# US_SB_BIC.net
KiCad netlist of a schematic drawn in Altium Designer
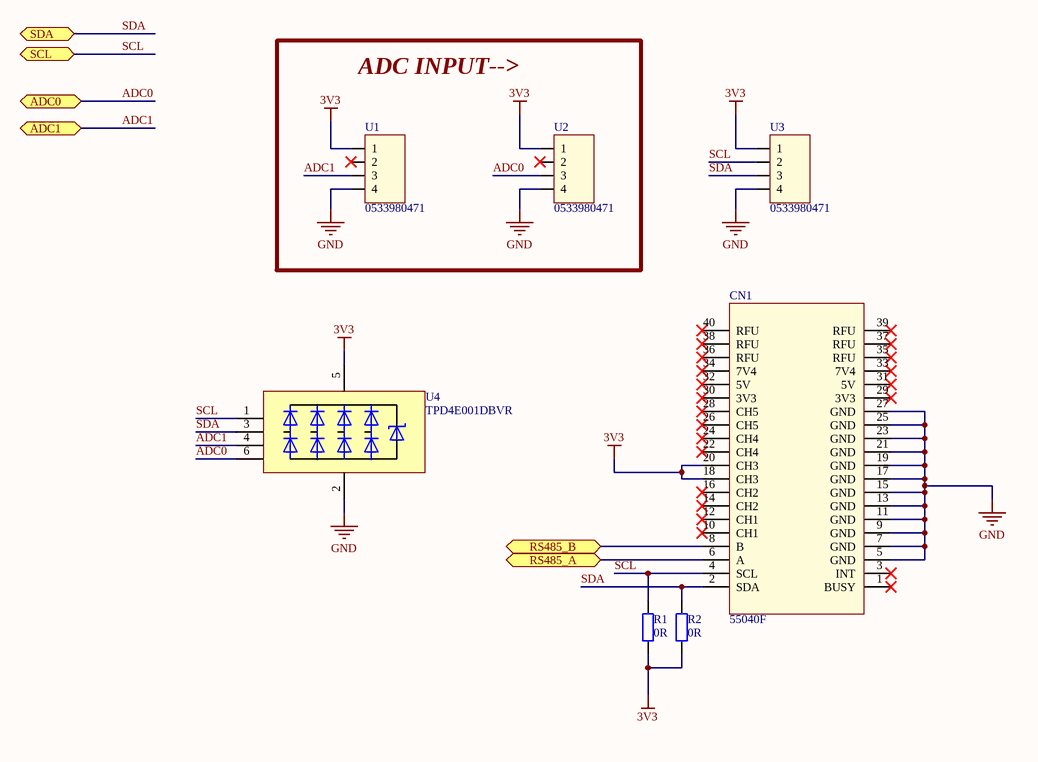
[diagram p0: US_SB_BIC.SchDoc]

(export (version "E")
  (design (tool "Eeschema 10.0.6"))
  (components
    (comp (ref "CN1")
      (value "55040F")
      (footprint "HEADER_40PIN_12MM2")
      (description "CONN HEADER R/A 40POS 2.54MM")
      (fields (field (name "MANUFACTURER") "On Shore Technology Inc."))
      (libsource (lib "alfasat_parts_lib") (part "ALFASAT_BIC"))
    )
    (comp (ref "R1")
      (value "0R")
      (footprint "R0603_IPC_MD")
      (description "RES SMD 0 OHM JUMPER 1/10W 0603")
      (fields
        (field (name "MANUFACTURER") "Bourns Inc.")
        (field (name "MANUFACTURER PART NUMBER") "CR0603-J/-000ELF")
      )
      (libsource (lib "alfasat_lib") (part "CR0603-J/-000ELF"))
    )
    (comp (ref "R2")
      (value "0R")
      (footprint "R0603_IPC_MD")
      (description "RES SMD 0 OHM JUMPER 1/10W 0603")
      (fields
        (field (name "MANUFACTURER") "Bourns Inc.")
        (field (name "MANUFACTURER PART NUMBER") "CR0603-J/-000ELF")
      )
      (libsource (lib "alfasat_lib") (part "CR0603-J/-000ELF"))
    )
    (comp (ref "U1")
      (value "0533980471")
      (footprint "PB_53261-0471_Right")
      (description "Connector Header Surface Mount 4 position 0.049\" (1.25mm)")
      (fields (field (name "MANUFACTURER") "Molex"))
      (libsource (lib "alfasat_lib_eps") (part "PB_053398_0471"))
    )
    (comp (ref "U2")
      (value "0533980471")
      (footprint "PB_53261-0471_Right")
      (description "Connector Header Surface Mount 4 position 0.049\" (1.25mm)")
      (fields (field (name "MANUFACTURER") "Molex"))
      (libsource (lib "alfasat_lib_eps") (part "PB_053398_0471"))
    )
    (comp (ref "U3")
      (value "0533980471")
      (footprint "PB_53261-0471_Right")
      (description "Connector Header Surface Mount 4 position 0.049\" (1.25mm)")
      (fields (field (name "MANUFACTURER") "Molex"))
      (libsource (lib "alfasat_lib_eps") (part "PB_053398_0471"))
    )
    (comp (ref "U4")
      (value "TPD4E001DBVR")
      (footprint "SOT23-6")
      (description "4x TVS DIODE 5.5V SOT23-6")
      (fields (field (name "MANUFACTURER") "TI"))
      (libsource (lib "alfasat_parts_lib") (part "TPD4E001DBVR"))
    )
  )
  (nets
    (net (code "1") (name "/ADC0") (class "Default")
      (node (ref "U2") (pin "3") (pinfunction "3_3") (pintype "passive"))
      (node (ref "U4") (pin "6") (pinfunction "IO4_6") (pintype "passive"))
    )
    (net (code "2") (name "/ADC1") (class "Default")
      (node (ref "U1") (pin "3") (pinfunction "3_3") (pintype "passive"))
      (node (ref "U4") (pin "4") (pinfunction "IO3_4") (pintype "passive"))
    )
    (net (code "3") (name "/RS485_A") (class "Default")
      (node (ref "CN1") (pin "6") (pinfunction "A_6") (pintype "passive"))
    )
    (net (code "4") (name "/RS485_B") (class "Default")
      (node (ref "CN1") (pin "8") (pinfunction "B_8") (pintype "passive"))
    )
    (net (code "5") (name "/SCL") (class "Default")
      (node (ref "CN1") (pin "4") (pinfunction "SCL_4") (pintype "passive"))
      (node (ref "R1") (pin "2") (pinfunction "2_2") (pintype "passive"))
      (node (ref "U3") (pin "2") (pinfunction "2_2") (pintype "passive"))
      (node (ref "U4") (pin "1") (pinfunction "IO1_1") (pintype "passive"))
    )
    (net (code "6") (name "/SDA") (class "Default")
      (node (ref "CN1") (pin "2") (pinfunction "SDA_2") (pintype "passive"))
      (node (ref "R2") (pin "2") (pinfunction "2_2") (pintype "passive"))
      (node (ref "U3") (pin "3") (pinfunction "3_3") (pintype "passive"))
      (node (ref "U4") (pin "3") (pinfunction "IO2_3") (pintype "passive"))
    )
    (net (code "7") (name "3V3") (class "Default")
      (node (ref "CN1") (pin "18") (pinfunction "CH3_18") (pintype "passive"))
      (node (ref "CN1") (pin "20") (pinfunction "CH3_20") (pintype "passive"))
      (node (ref "R1") (pin "1") (pinfunction "1_1") (pintype "passive"))
      (node (ref "R2") (pin "1") (pinfunction "1_1") (pintype "passive"))
      (node (ref "U1") (pin "1") (pinfunction "1_1") (pintype "passive"))
      (node (ref "U2") (pin "1") (pinfunction "1_1") (pintype "passive"))
      (node (ref "U3") (pin "1") (pinfunction "1_1") (pintype "passive"))
      (node (ref "U4") (pin "5") (pinfunction "VCC_5") (pintype "power_in"))
    )
    (net (code "8") (name "GND") (class "Default")
      (node (ref "CN1") (pin "11") (pinfunction "GND_11") (pintype "passive"))
      (node (ref "CN1") (pin "13") (pinfunction "GND_13") (pintype "passive"))
      (node (ref "CN1") (pin "15") (pinfunction "GND_15") (pintype "passive"))
      (node (ref "CN1") (pin "17") (pinfunction "GND_17") (pintype "passive"))
      (node (ref "CN1") (pin "19") (pinfunction "GND_19") (pintype "passive"))
      (node (ref "CN1") (pin "21") (pinfunction "GND_21") (pintype "passive"))
      (node (ref "CN1") (pin "23") (pinfunction "GND_23") (pintype "passive"))
      (node (ref "CN1") (pin "25") (pinfunction "GND_25") (pintype "passive"))
      (node (ref "CN1") (pin "27") (pinfunction "GND_27") (pintype "passive"))
      (node (ref "CN1") (pin "5") (pinfunction "GND_5") (pintype "passive"))
      (node (ref "CN1") (pin "7") (pinfunction "GND_7") (pintype "passive"))
      (node (ref "CN1") (pin "9") (pinfunction "GND_9") (pintype "passive"))
      (node (ref "U1") (pin "4") (pinfunction "4_4") (pintype "passive"))
      (node (ref "U2") (pin "4") (pinfunction "4_4") (pintype "passive"))
      (node (ref "U3") (pin "4") (pinfunction "4_4") (pintype "passive"))
      (node (ref "U4") (pin "2") (pinfunction "GND_2") (pintype "power_in"))
    )
    (net (code "9") (name "unconnected-(CN1-3V3-Pad29)") (class "Default")
      (node (ref "CN1") (pin "29") (pinfunction "3V3_29") (pintype "passive+no_connect"))
    )
    (net (code "10") (name "unconnected-(CN1-3V3-Pad30)") (class "Default")
      (node (ref "CN1") (pin "30") (pinfunction "3V3_30") (pintype "passive+no_connect"))
    )
    (net (code "11") (name "unconnected-(CN1-5V-Pad31)") (class "Default")
      (node (ref "CN1") (pin "31") (pinfunction "5V_31") (pintype "passive+no_connect"))
    )
    (net (code "12") (name "unconnected-(CN1-5V-Pad32)") (class "Default")
      (node (ref "CN1") (pin "32") (pinfunction "5V_32") (pintype "passive+no_connect"))
    )
    (net (code "13") (name "unconnected-(CN1-7V4-Pad33)") (class "Default")
      (node (ref "CN1") (pin "33") (pinfunction "7V4_33") (pintype "passive+no_connect"))
    )
    (net (code "14") (name "unconnected-(CN1-7V4-Pad34)") (class "Default")
      (node (ref "CN1") (pin "34") (pinfunction "7V4_34") (pintype "passive+no_connect"))
    )
    (net (code "15") (name "unconnected-(CN1-BUSY-Pad1)") (class "Default")
      (node (ref "CN1") (pin "1") (pinfunction "BUSY_1") (pintype "passive+no_connect"))
    )
    (net (code "16") (name "unconnected-(CN1-CH1-Pad10)") (class "Default")
      (node (ref "CN1") (pin "10") (pinfunction "CH1_10") (pintype "passive+no_connect"))
    )
    (net (code "17") (name "unconnected-(CN1-CH1-Pad12)") (class "Default")
      (node (ref "CN1") (pin "12") (pinfunction "CH1_12") (pintype "passive+no_connect"))
    )
    (net (code "18") (name "unconnected-(CN1-CH2-Pad14)") (class "Default")
      (node (ref "CN1") (pin "14") (pinfunction "CH2_14") (pintype "passive+no_connect"))
    )
    (net (code "19") (name "unconnected-(CN1-CH2-Pad16)") (class "Default")
      (node (ref "CN1") (pin "16") (pinfunction "CH2_16") (pintype "passive+no_connect"))
    )
    (net (code "20") (name "unconnected-(CN1-CH4-Pad22)") (class "Default")
      (node (ref "CN1") (pin "22") (pinfunction "CH4_22") (pintype "passive+no_connect"))
    )
    (net (code "21") (name "unconnected-(CN1-CH4-Pad24)") (class "Default")
      (node (ref "CN1") (pin "24") (pinfunction "CH4_24") (pintype "passive+no_connect"))
    )
    (net (code "22") (name "unconnected-(CN1-CH5-Pad26)") (class "Default")
      (node (ref "CN1") (pin "26") (pinfunction "CH5_26") (pintype "passive+no_connect"))
    )
    (net (code "23") (name "unconnected-(CN1-CH5-Pad28)") (class "Default")
      (node (ref "CN1") (pin "28") (pinfunction "CH5_28") (pintype "passive+no_connect"))
    )
    (net (code "24") (name "unconnected-(CN1-INT-Pad3)") (class "Default")
      (node (ref "CN1") (pin "3") (pinfunction "INT_3") (pintype "passive+no_connect"))
    )
    (net (code "25") (name "unconnected-(CN1-RFU-Pad35)") (class "Default")
      (node (ref "CN1") (pin "35") (pinfunction "RFU_35") (pintype "passive+no_connect"))
    )
    (net (code "26") (name "unconnected-(CN1-RFU-Pad36)") (class "Default")
      (node (ref "CN1") (pin "36") (pinfunction "RFU_36") (pintype "passive+no_connect"))
    )
    (net (code "27") (name "unconnected-(CN1-RFU-Pad37)") (class "Default")
      (node (ref "CN1") (pin "37") (pinfunction "RFU_37") (pintype "passive+no_connect"))
    )
    (net (code "28") (name "unconnected-(CN1-RFU-Pad38)") (class "Default")
      (node (ref "CN1") (pin "38") (pinfunction "RFU_38") (pintype "passive+no_connect"))
    )
    (net (code "29") (name "unconnected-(CN1-RFU-Pad39)") (class "Default")
      (node (ref "CN1") (pin "39") (pinfunction "RFU_39") (pintype "passive+no_connect"))
    )
    (net (code "30") (name "unconnected-(CN1-RFU-Pad40)") (class "Default")
      (node (ref "CN1") (pin "40") (pinfunction "RFU_40") (pintype "passive+no_connect"))
    )
    (net (code "31") (name "unconnected-(U1-Pad2)") (class "Default")
      (node (ref "U1") (pin "2") (pinfunction "2_2") (pintype "passive+no_connect"))
    )
    (net (code "32") (name "unconnected-(U2-Pad2)") (class "Default")
      (node (ref "U2") (pin "2") (pinfunction "2_2") (pintype "passive+no_connect"))
    )
  )
)
